# P04_MCU.net
KiCad netlist of a schematic drawn in Altium Designer
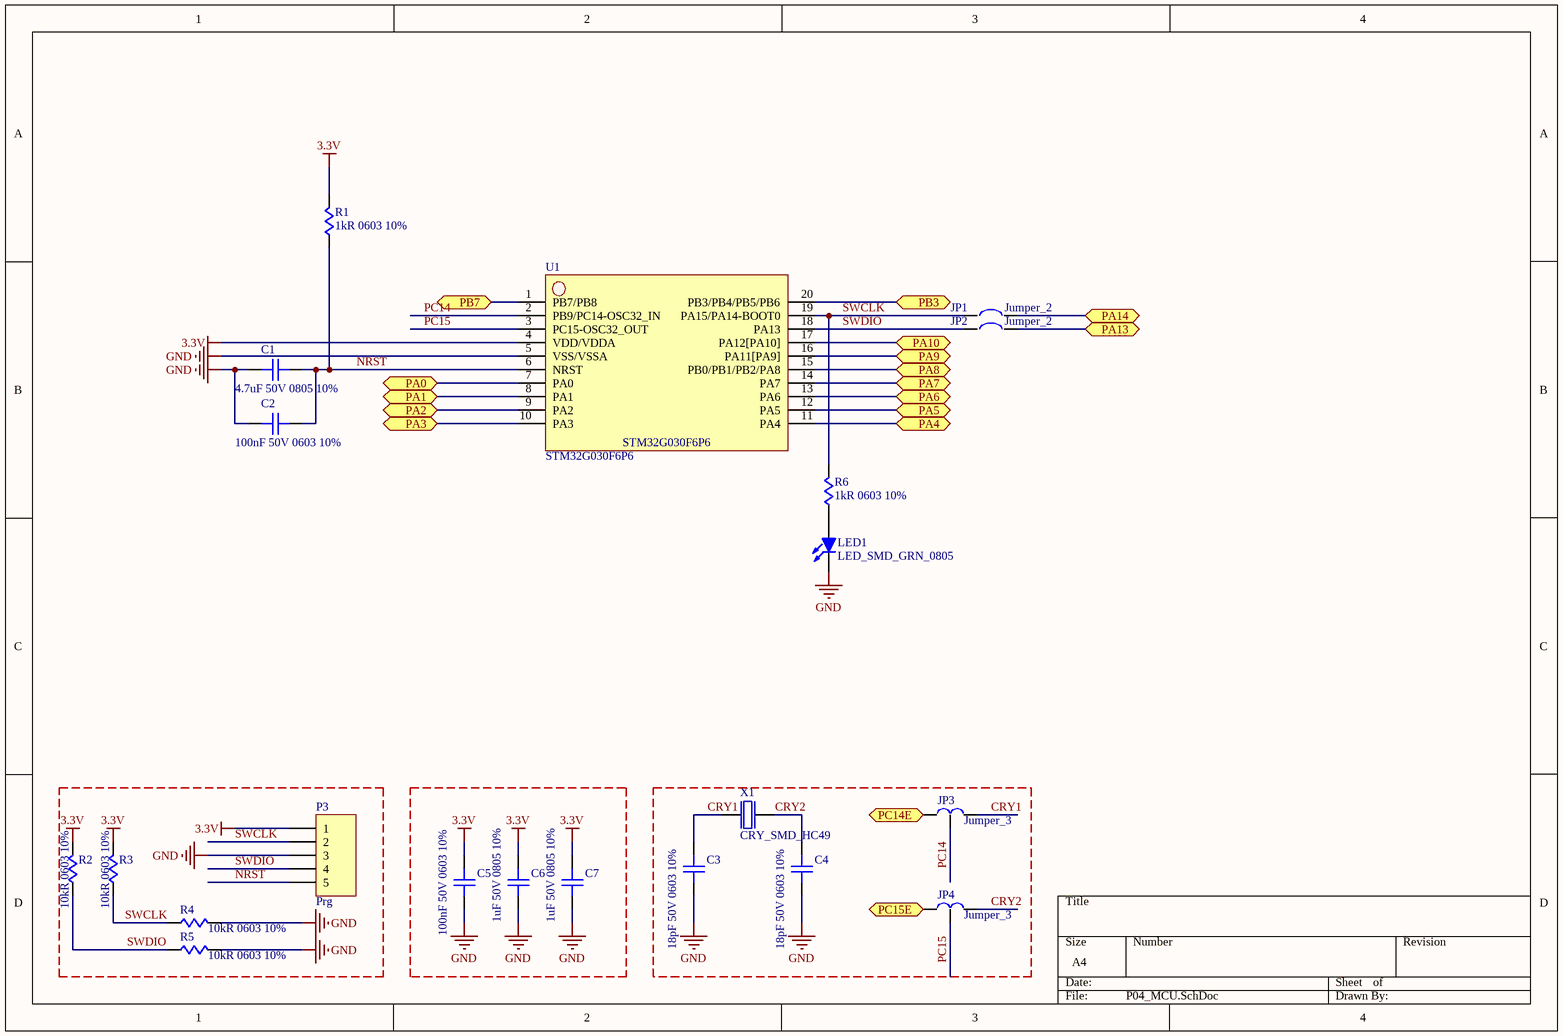
[diagram p0: P04_MCU.SchDoc]

(export (version "E")
  (design (tool "Eeschema 10.0.6"))
  (components
    (comp (ref "C1")
      (value "4.7uF 50V 0805 10%")
      (footprint "CAPC-0805-M")
      (libsource (lib "esaltlib20") (part "CAP_SMD_0805"))
    )
    (comp (ref "C2")
      (value "100nF 50V 0603 10%")
      (footprint "CAPC-0603-M")
      (libsource (lib "esaltlib20") (part "CAP_SMD_0603"))
    )
    (comp (ref "C3")
      (value "18pF 50V 0603 10%")
      (footprint "CAPC-0603-M")
      (libsource (lib "esaltlib20") (part "CAP_SMD_0603"))
    )
    (comp (ref "C4")
      (value "18pF 50V 0603 10%")
      (footprint "CAPC-0603-M")
      (libsource (lib "esaltlib20") (part "CAP_SMD_0603"))
    )
    (comp (ref "C5")
      (value "100nF 50V 0603 10%")
      (footprint "CAPC-0603-M")
      (libsource (lib "esaltlib20") (part "CAP_SMD_0603"))
    )
    (comp (ref "C6")
      (value "1uF 50V 0805 10%")
      (footprint "CAPC-0805-M")
      (libsource (lib "esaltlib20") (part "CAP_SMD_0805"))
    )
    (comp (ref "C7")
      (value "1uF 50V 0805 10%")
      (footprint "CAPC-0805-M")
      (libsource (lib "esaltlib20") (part "CAP_SMD_0805"))
    )
    (comp (ref "JP1")
      (value "Jumper_2")
      (footprint "JMP_SMD_2")
      (libsource (lib "esaltlib20") (part "Jumper_2"))
    )
    (comp (ref "JP2")
      (value "Jumper_2")
      (footprint "JMP_SMD_2")
      (libsource (lib "esaltlib20") (part "Jumper_2"))
    )
    (comp (ref "JP3")
      (value "Jumper_3")
      (footprint "JMP_SMD_3")
      (libsource (lib "esaltlib20") (part "Jumper_3"))
    )
    (comp (ref "JP4")
      (value "Jumper_3")
      (footprint "JMP_SMD_3")
      (libsource (lib "esaltlib20") (part "Jumper_3"))
    )
    (comp (ref "LED1")
      (value "LED_SMD_GRN_0805")
      (footprint "LED-GRN-0805-M")
      (libsource (lib "esaltlib20") (part "LED_SMD_GRN_0805"))
    )
    (comp (ref "P3")
      (value "Prg")
      (footprint "HDR_1_5_M_180")
      (description "Header, 5-Pin")
      (fields (field (name "PUBLISHER") "Altium Limited"))
      (libsource (lib "esaltlib20") (part "Header 5"))
    )
    (comp (ref "R1")
      (value "1kR 0603 10%")
      (footprint "RESC-0603-M")
      (libsource (lib "esaltlib20") (part "RES_SMD_0603"))
    )
    (comp (ref "R2")
      (value "10kR 0603 10%")
      (footprint "RESC-0603-M")
      (libsource (lib "esaltlib20") (part "RES_SMD_0603"))
    )
    (comp (ref "R3")
      (value "10kR 0603 10%")
      (footprint "RESC-0603-M")
      (libsource (lib "esaltlib20") (part "RES_SMD_0603"))
    )
    (comp (ref "R4")
      (value "10kR 0603 10%")
      (footprint "RESC-0603-M")
      (libsource (lib "esaltlib20") (part "RES_SMD_0603"))
    )
    (comp (ref "R5")
      (value "10kR 0603 10%")
      (footprint "RESC-0603-M")
      (libsource (lib "esaltlib20") (part "RES_SMD_0603"))
    )
    (comp (ref "R6")
      (value "1kR 0603 10%")
      (footprint "RESC-0603-M")
      (libsource (lib "esaltlib20") (part "RES_SMD_0603"))
    )
    (comp (ref "U1")
      (value "STM32G030F6P6")
      (footprint "TSOP-20-M")
      (libsource (lib "esaltlib20") (part "STM32G030F6P6"))
    )
    (comp (ref "X1")
      (value "CRY_SMD_HC49")
      (footprint "HC49 US")
      (libsource (lib "esaltlib20") (part "CRY_SMD_HC49"))
    )
  )
  (nets
    (net (code "1") (name "/CRY1") (class "Default")
      (node (ref "C3") (pin "1") (pinfunction "1_1") (pintype "passive"))
      (node (ref "JP3") (pin "3") (pinfunction "C_3") (pintype "passive"))
      (node (ref "X1") (pin "1") (pinfunction "A_1") (pintype "passive"))
    )
    (net (code "2") (name "/CRY2") (class "Default")
      (node (ref "C4") (pin "1") (pinfunction "1_1") (pintype "passive"))
      (node (ref "JP4") (pin "3") (pinfunction "C_3") (pintype "passive"))
      (node (ref "X1") (pin "2") (pinfunction "B_2") (pintype "passive"))
    )
    (net (code "3") (name "/NRST") (class "Default")
      (node (ref "C1") (pin "1") (pinfunction "1_1") (pintype "passive"))
      (node (ref "C2") (pin "1") (pinfunction "1_1") (pintype "passive"))
      (node (ref "P3") (pin "5") (pinfunction "5_5") (pintype "passive"))
      (node (ref "R1") (pin "1") (pinfunction "A_1") (pintype "passive"))
      (node (ref "U1") (pin "6") (pinfunction "NRST_6") (pintype "power_in"))
    )
    (net (code "4") (name "/PA0") (class "Default")
      (node (ref "U1") (pin "7") (pinfunction "PA0_7") (pintype "power_in"))
    )
    (net (code "5") (name "/PA1") (class "Default")
      (node (ref "U1") (pin "8") (pinfunction "PA1_8") (pintype "power_in"))
    )
    (net (code "6") (name "/PA2") (class "Default")
      (node (ref "U1") (pin "9") (pinfunction "PA2_9") (pintype "power_in"))
    )
    (net (code "7") (name "/PA3") (class "Default")
      (node (ref "U1") (pin "10") (pinfunction "PA3_10") (pintype "power_in"))
    )
    (net (code "8") (name "/PA4") (class "Default")
      (node (ref "U1") (pin "11") (pinfunction "PA4_11") (pintype "power_in"))
    )
    (net (code "9") (name "/PA5") (class "Default")
      (node (ref "U1") (pin "12") (pinfunction "PA5_12") (pintype "power_in"))
    )
    (net (code "10") (name "/PA6") (class "Default")
      (node (ref "U1") (pin "13") (pinfunction "PA6_13") (pintype "power_in"))
    )
    (net (code "11") (name "/PA7") (class "Default")
      (node (ref "U1") (pin "14") (pinfunction "PA7_14") (pintype "power_in"))
    )
    (net (code "12") (name "/PA8") (class "Default")
      (node (ref "U1") (pin "15") (pinfunction "PB0/PB1/PB2/PA8_15") (pintype "power_in"))
    )
    (net (code "13") (name "/PA9") (class "Default")
      (node (ref "U1") (pin "16") (pinfunction "PA11[PA9]_16") (pintype "power_in"))
    )
    (net (code "14") (name "/PA10") (class "Default")
      (node (ref "U1") (pin "17") (pinfunction "PA12[PA10]_17") (pintype "power_in"))
    )
    (net (code "15") (name "/PA13") (class "Default")
      (node (ref "JP2") (pin "2") (pinfunction "B_2") (pintype "passive"))
    )
    (net (code "16") (name "/PA14") (class "Default")
      (node (ref "JP1") (pin "2") (pinfunction "B_2") (pintype "passive"))
    )
    (net (code "17") (name "/PB3") (class "Default")
      (node (ref "U1") (pin "20") (pinfunction "PB3/PB4/PB5/PB6_20") (pintype "power_in"))
    )
    (net (code "18") (name "/PB7") (class "Default")
      (node (ref "U1") (pin "1") (pinfunction "PB7/PB8_1") (pintype "power_in"))
    )
    (net (code "19") (name "/PC14") (class "Default")
      (node (ref "JP3") (pin "2") (pinfunction "B_2") (pintype "passive"))
      (node (ref "U1") (pin "2") (pinfunction "PB9/PC14-OSC32_IN_2") (pintype "power_in"))
    )
    (net (code "20") (name "/PC14E") (class "Default")
      (node (ref "JP3") (pin "1") (pinfunction "A_1") (pintype "passive"))
    )
    (net (code "21") (name "/PC15") (class "Default")
      (node (ref "JP4") (pin "2") (pinfunction "B_2") (pintype "passive"))
      (node (ref "U1") (pin "3") (pinfunction "PC15-OSC32_OUT_3") (pintype "power_in"))
    )
    (net (code "22") (name "/PC15E") (class "Default")
      (node (ref "JP4") (pin "1") (pinfunction "A_1") (pintype "passive"))
    )
    (net (code "23") (name "/SWCLK") (class "Default")
      (node (ref "JP1") (pin "1") (pinfunction "A_1") (pintype "passive"))
      (node (ref "P3") (pin "2") (pinfunction "2_2") (pintype "passive"))
      (node (ref "R3") (pin "1") (pinfunction "A_1") (pintype "passive"))
      (node (ref "R4") (pin "1") (pinfunction "A_1") (pintype "passive"))
      (node (ref "R6") (pin "2") (pinfunction "B_2") (pintype "passive"))
      (node (ref "U1") (pin "19") (pinfunction "PA15/PA14-BOOT0_19") (pintype "power_in"))
    )
    (net (code "24") (name "/SWDIO") (class "Default")
      (node (ref "JP2") (pin "1") (pinfunction "A_1") (pintype "passive"))
      (node (ref "P3") (pin "4") (pinfunction "4_4") (pintype "passive"))
      (node (ref "R2") (pin "1") (pinfunction "A_1") (pintype "passive"))
      (node (ref "R5") (pin "1") (pinfunction "A_1") (pintype "passive"))
      (node (ref "U1") (pin "18") (pinfunction "PA13_18") (pintype "power_in"))
    )
    (net (code "25") (name "3.3V") (class "Default")
      (node (ref "C5") (pin "1") (pinfunction "1_1") (pintype "passive"))
      (node (ref "C6") (pin "1") (pinfunction "1_1") (pintype "passive"))
      (node (ref "C7") (pin "1") (pinfunction "1_1") (pintype "passive"))
      (node (ref "P3") (pin "1") (pinfunction "1_1") (pintype "passive"))
      (node (ref "R1") (pin "2") (pinfunction "B_2") (pintype "passive"))
      (node (ref "R2") (pin "2") (pinfunction "B_2") (pintype "passive"))
      (node (ref "R3") (pin "2") (pinfunction "B_2") (pintype "passive"))
      (node (ref "U1") (pin "4") (pinfunction "VDD/VDDA_4") (pintype "power_in"))
    )
    (net (code "26") (name "GND") (class "Default")
      (node (ref "C1") (pin "2") (pinfunction "2_2") (pintype "passive"))
      (node (ref "C2") (pin "2") (pinfunction "2_2") (pintype "passive"))
      (node (ref "C3") (pin "2") (pinfunction "2_2") (pintype "passive"))
      (node (ref "C4") (pin "2") (pinfunction "2_2") (pintype "passive"))
      (node (ref "C5") (pin "2") (pinfunction "2_2") (pintype "passive"))
      (node (ref "C6") (pin "2") (pinfunction "2_2") (pintype "passive"))
      (node (ref "C7") (pin "2") (pinfunction "2_2") (pintype "passive"))
      (node (ref "LED1") (pin "2") (pinfunction "K_2") (pintype "passive"))
      (node (ref "P3") (pin "3") (pinfunction "3_3") (pintype "passive"))
      (node (ref "R4") (pin "2") (pinfunction "B_2") (pintype "passive"))
      (node (ref "R5") (pin "2") (pinfunction "B_2") (pintype "passive"))
      (node (ref "U1") (pin "5") (pinfunction "VSS/VSSA_5") (pintype "power_in"))
    )
    (net (code "27") (name "Net-(LED1-A)") (class "Default")
      (node (ref "LED1") (pin "1") (pinfunction "A_1") (pintype "passive"))
      (node (ref "R6") (pin "1") (pinfunction "A_1") (pintype "passive"))
    )
  )
)
